# Flyback.net
KiCad netlist of a schematic drawn in Altium Designer
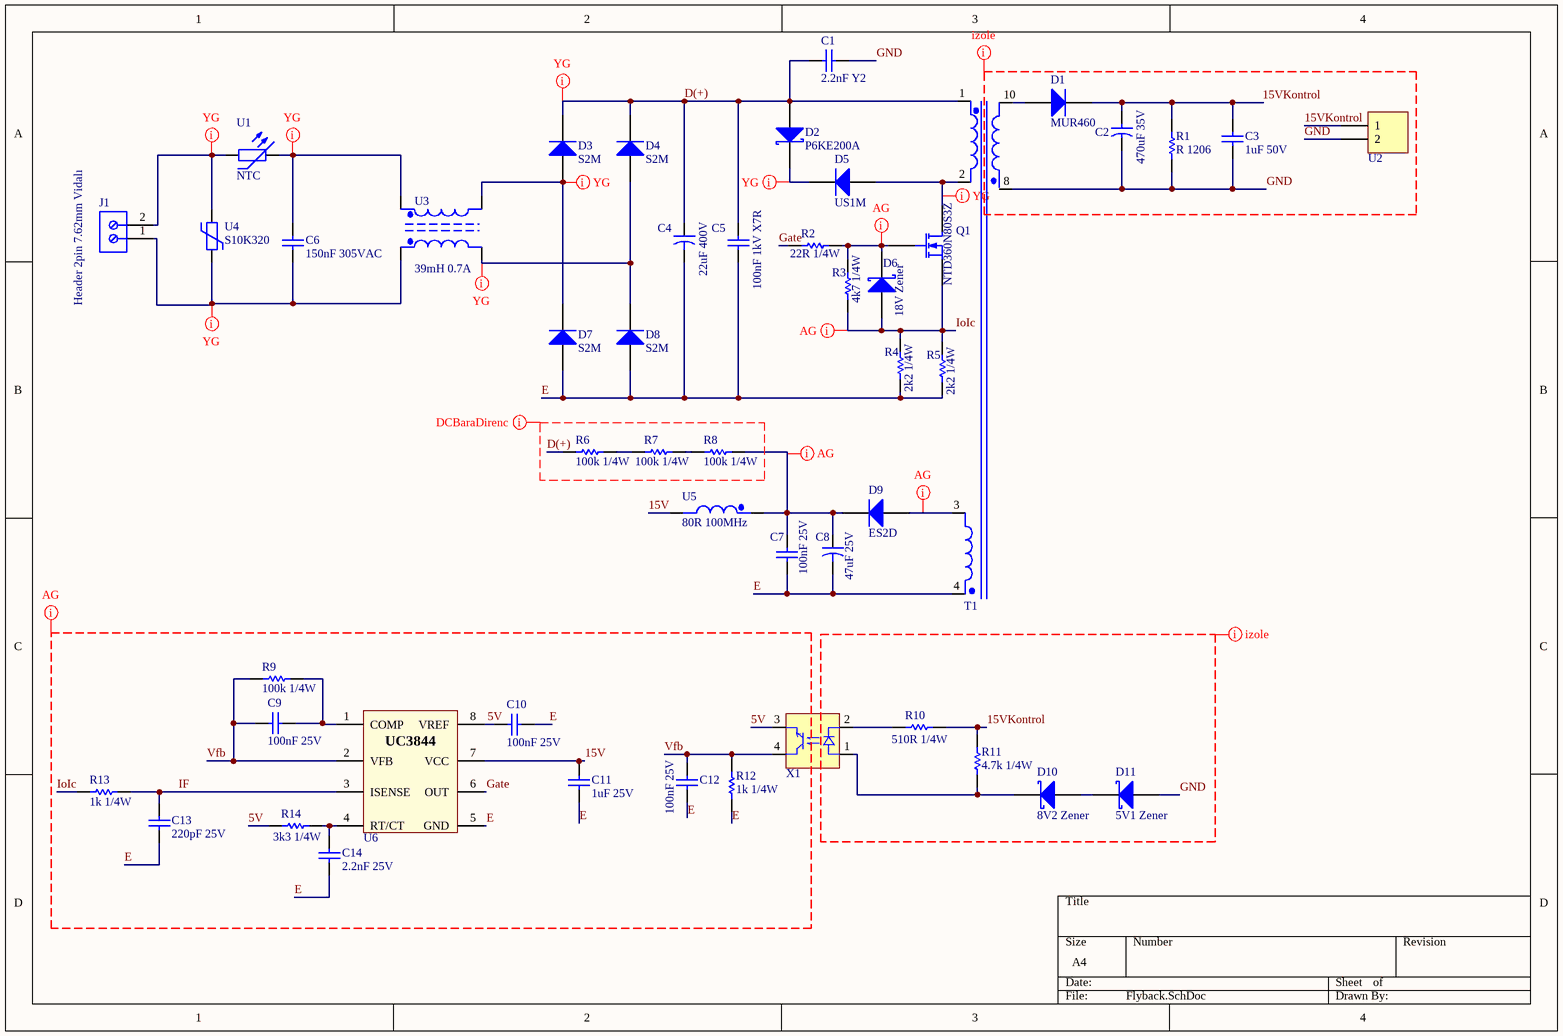
[diagram p0: Flyback.SchDoc]

(export (version "E")
  (design (tool "Eeschema 10.0.6"))
  (components
    (comp (ref "C1")
      (value "2.2nF Y2")
      (footprint "Footprint-Lib-Zhrzkn:4x13x9")
      (description "495-4967-1-ND")
      (fields (field (name "PUBLISHER") "Altium Limited") (field (name "DESIGNER") "ZehraOzkan"))
      (libsource (lib "Schematic-Lib-Zhrzkn") (part "Cap Y2 2.2nF 300V MKP TDK"))
    )
    (comp (ref "C2")
      (value "470uF 35V")
      (footprint "Footprint-Lib-Zhrzkn:CAPPRD500W60D1025H1750")
      (description "860040475008")
      (fields (field (name "PUBLISHER") "Altium Limited") (field (name "DESIGNER") "ZehraOzkan"))
      (libsource (lib "Schematic-Lib-Zhrzkn") (part "C 470uF 35V 1.76A 28mOhm"))
    )
    (comp (ref "C3")
      (value "1uF 50V")
      (footprint "Footprint-Lib-Zhrzkn:1206")
      (description "SMD 1206")
      (fields (field (name "DESIGNER") "ZehraOzkan"))
      (libsource (lib "Schematic-Lib-Zhrzkn") (part "C 1206"))
    )
    (comp (ref "C4")
      (value "22uF 400V")
      (footprint "Footprint-Lib-Zhrzkn:22uF 400V")
      (description "400AX22MEFC12.5X16")
      (fields
        (field (name "MANUFACTURER_PART_NUMBER") "TPSE107K020R0150")
        (field (name "MOUSER PART NUMBER") "581-TPSE107K020R0150")
        (field (name "DESIGNER") "ZehraOzkan")
      )
      (libsource (lib "Schematic-Lib-Zhrzkn") (part "C 22uF 400V 270mArms"))
    )
    (comp (ref "C5")
      (value "100nF 1kV X7R")
      (footprint "RCE7U2J333J5B1H03B")
      (description "490-8944-ND")
      (fields (field (name "PUBLISHER") "Altium Limited") (field (name "DESIGNER") "ZehraOzkan"))
      (libsource (lib "Schematic-Lib-Zhrzkn") (part "C Seramik 100nF 1kV X7R 5mm"))
    )
    (comp (ref "C6")
      (value "150nF 305VAC")
      (footprint "Footprint-Lib-Zhrzkn:CFR F15 L18 B6 H12")
      (description "1572-1789-ND")
      (fields
        (field (name "PART NUMBER") "890273322005CS")
        (field (name "PUBLISHER") "Wurth Elektronik")
        (field (name "DESIGNER") "ZehraOzkan")
      )
      (libsource (lib "Schematic-Lib-Zhrzkn") (part "Cap 150nF 305VAC X2"))
    )
    (comp (ref "C7")
      (value "100nF 25V")
      (footprint "Footprint-Lib-Zhrzkn:1206")
      (description "SMD 1206")
      (fields (field (name "DESIGNER") "ZehraOzkan"))
      (libsource (lib "Schematic-Lib-Zhrzkn") (part "C 1206"))
    )
    (comp (ref "C8")
      (value "47uF 25V")
      (footprint "Footprint-Lib-Zhrzkn:CAPPRD200W50D525H1250")
      (description "1189-1590-1-ND")
      (fields (field (name "DESIGNER") "ZehraOzkan"))
      (libsource (lib "Schematic-Lib-Zhrzkn") (part "C 47uF 25V 250mArms 400mOhm"))
    )
    (comp (ref "C9")
      (value "100nF 25V")
      (footprint "Footprint-Lib-Zhrzkn:1206")
      (description "SMD 1206")
      (fields (field (name "DESIGNER") "ZehraOzkan"))
      (libsource (lib "Schematic-Lib-Zhrzkn") (part "C 1206"))
    )
    (comp (ref "C10")
      (value "100nF 25V")
      (footprint "Footprint-Lib-Zhrzkn:1206")
      (description "SMD 1206")
      (fields (field (name "DESIGNER") "ZehraOzkan"))
      (libsource (lib "Schematic-Lib-Zhrzkn") (part "C 1206"))
    )
    (comp (ref "C11")
      (value "1uF 25V")
      (footprint "Footprint-Lib-Zhrzkn:1206")
      (description "SMD 1206")
      (fields (field (name "DESIGNER") "ZehraOzkan"))
      (libsource (lib "Schematic-Lib-Zhrzkn") (part "C 1206"))
    )
    (comp (ref "C12")
      (value "100nF 25V")
      (footprint "Footprint-Lib-Zhrzkn:1206")
      (description "SMD 1206")
      (fields (field (name "DESIGNER") "ZehraOzkan"))
      (libsource (lib "Schematic-Lib-Zhrzkn") (part "C 1206"))
    )
    (comp (ref "C13")
      (value "220pF 25V")
      (footprint "Footprint-Lib-Zhrzkn:1206")
      (description "SMD 1206")
      (fields (field (name "DESIGNER") "ZehraOzkan"))
      (libsource (lib "Schematic-Lib-Zhrzkn") (part "C 1206"))
    )
    (comp (ref "C14")
      (value "2.2nF 25V")
      (footprint "Footprint-Lib-Zhrzkn:1206")
      (description "SMD 1206")
      (fields (field (name "DESIGNER") "ZehraOzkan"))
      (libsource (lib "Schematic-Lib-Zhrzkn") (part "C 1206"))
    )
    (comp (ref "D1")
      (value "MUR460")
      (footprint "DO-201AD -Dik")
      (description "MUR460RLGOSCT-ND")
      (fields (field (name "DESIGNER") "ZehraOzkan"))
      (libsource (lib "Schematic-Lib-Zhrzkn") (part "Diyot DO-201AD Dik"))
    )
    (comp (ref "D2")
      (value "P6KE200A")
      (footprint "DO-15((DO-204AC)")
      (description "497-13419-1-ND")
      (fields (field (name "PUBLISHER") "Altium Limited") (field (name "DESIGNER") "ZehraOzkan"))
      (libsource (lib "Schematic-Lib-Zhrzkn") (part "TVS 200V DO-15"))
    )
    (comp (ref "D3")
      (value "S2M")
      (footprint "DO-214AA(SMB)")
      (description "1655-1N4007FLCT-ND")
      (fields (field (name "DESIGNER") "ZehraOzkan"))
      (libsource (lib "Schematic-Lib-Zhrzkn") (part "D 1N4007 DO-214AA(SMB)"))
    )
    (comp (ref "D4")
      (value "S2M")
      (footprint "DO-214AA(SMB)")
      (description "1655-1N4007FLCT-ND")
      (fields (field (name "DESIGNER") "ZehraOzkan"))
      (libsource (lib "Schematic-Lib-Zhrzkn") (part "D 1N4007 DO-214AA(SMB)"))
    )
    (comp (ref "D5")
      (value "US1M")
      (footprint "DO-214AA(SMB)")
      (description "SMA")
      (fields (field (name "DESIGNER") "ZehraOzkan"))
      (libsource (lib "Schematic-Lib-Zhrzkn") (part "US1M"))
    )
    (comp (ref "D6")
      (value "18V Zener")
      (footprint "SOD-123")
      (description "SOD-123")
      (fields (field (name "PUBLISHER") "Altium Limited") (field (name "DESIGNER") "ZehraOzkan"))
      (libsource (lib "Schematic-Lib-Zhrzkn") (part "Zener SOD-123_1"))
    )
    (comp (ref "D7")
      (value "S2M")
      (footprint "DO-214AA(SMB)")
      (description "1655-1N4007FLCT-ND")
      (fields (field (name "DESIGNER") "ZehraOzkan"))
      (libsource (lib "Schematic-Lib-Zhrzkn") (part "D 1N4007 DO-214AA(SMB)"))
    )
    (comp (ref "D8")
      (value "S2M")
      (footprint "DO-214AA(SMB)")
      (description "1655-1N4007FLCT-ND")
      (fields (field (name "DESIGNER") "ZehraOzkan"))
      (libsource (lib "Schematic-Lib-Zhrzkn") (part "D 1N4007 DO-214AA(SMB)"))
    )
    (comp (ref "D9")
      (value "ES2D")
      (footprint "DO-214AA(SMB)")
      (description "ES2DFSCT-ND")
      (fields (field (name "DESIGNER") "ZehraOzkan"))
      (libsource (lib "Schematic-Lib-Zhrzkn") (part "D ES2D"))
    )
    (comp (ref "D10")
      (value "8V2 Zener")
      (footprint "SOD-123")
      (description "SOD-123")
      (fields (field (name "PUBLISHER") "Altium Limited") (field (name "DESIGNER") "ZehraOzkan"))
      (libsource (lib "Schematic-Lib-Zhrzkn") (part "Zener SOD-123_1"))
    )
    (comp (ref "D11")
      (value "5V1 Zener")
      (footprint "SOD-123")
      (description "SOD-123")
      (fields (field (name "PUBLISHER") "Altium Limited") (field (name "DESIGNER") "ZehraOzkan"))
      (libsource (lib "Schematic-Lib-Zhrzkn") (part "Zener SOD-123_1"))
    )
    (comp (ref "J1")
      (value "Header 2pin 7.62mm Vidalı")
      (footprint "Header 2 Pin 7.62mm Vidalı")
      (description "691214410002")
      (fields
        (field (name "PART NUMBER") "691218410002")
        (field (name "PUBLISHER") "Wurth Elektronik")
        (field (name "DESIGNER") "ZehraOzkan")
      )
      (libsource (lib "Schematic-Lib-Zhrzkn") (part "Header 2pin 7.62mm Vidalı"))
    )
    (comp (ref "Q1")
      (value "NTD360N80S3Z")
      (footprint "DPAK IGBT")
      (description "DPAK")
      (fields (field (name "PUBLISHER") "Altium Limited") (field (name "DESIGNER") "ZehraOzkan"))
      (libsource (lib "Schematic-Lib-Zhrzkn") (part "MOSFET DPAK"))
    )
    (comp (ref "R1")
      (value "R 1206")
      (footprint "RES_1206")
      (description "SMD 1206")
      (fields (field (name "DESIGNER") "ZehraOzkan"))
      (libsource (lib "Schematic-Lib-Zhrzkn") (part "R 1206"))
    )
    (comp (ref "R2")
      (value "22R 1/4W")
      (footprint "RES_1206")
      (description "SMD 1206")
      (fields (field (name "DESIGNER") "ZehraOzkan"))
      (libsource (lib "Schematic-Lib-Zhrzkn") (part "R 1206"))
    )
    (comp (ref "R3")
      (value "4k7 1/4W")
      (footprint "RES_1206")
      (description "SMD 1206")
      (fields (field (name "DESIGNER") "ZehraOzkan"))
      (libsource (lib "Schematic-Lib-Zhrzkn") (part "R 1206"))
    )
    (comp (ref "R4")
      (value "2k2 1/4W")
      (footprint "RES_1206")
      (description "SMD 1206")
      (fields (field (name "DESIGNER") "ZehraOzkan"))
      (libsource (lib "Schematic-Lib-Zhrzkn") (part "R 1206"))
    )
    (comp (ref "R5")
      (value "2k2 1/4W")
      (footprint "RES_1206")
      (description "SMD 1206")
      (fields (field (name "DESIGNER") "ZehraOzkan"))
      (libsource (lib "Schematic-Lib-Zhrzkn") (part "R 1206"))
    )
    (comp (ref "R6")
      (value "100k 1/4W")
      (footprint "RES_1206")
      (description "SMD 1206")
      (fields (field (name "DESIGNER") "ZehraOzkan"))
      (libsource (lib "Schematic-Lib-Zhrzkn") (part "R 1206"))
    )
    (comp (ref "R7")
      (value "100k 1/4W")
      (footprint "RES_1206")
      (description "SMD 1206")
      (fields (field (name "DESIGNER") "ZehraOzkan"))
      (libsource (lib "Schematic-Lib-Zhrzkn") (part "R 1206"))
    )
    (comp (ref "R8")
      (value "100k 1/4W")
      (footprint "RES_1206")
      (description "SMD 1206")
      (fields (field (name "DESIGNER") "ZehraOzkan"))
      (libsource (lib "Schematic-Lib-Zhrzkn") (part "R 1206"))
    )
    (comp (ref "R9")
      (value "100k 1/4W")
      (footprint "RES_1206")
      (description "SMD 1206")
      (fields (field (name "DESIGNER") "ZehraOzkan"))
      (libsource (lib "Schematic-Lib-Zhrzkn") (part "R 1206"))
    )
    (comp (ref "R10")
      (value "510R 1/4W")
      (footprint "RES_1206")
      (description "SMD 1206")
      (fields (field (name "DESIGNER") "ZehraOzkan"))
      (libsource (lib "Schematic-Lib-Zhrzkn") (part "R 1206"))
    )
    (comp (ref "R11")
      (value "4.7k 1/4W")
      (footprint "RES_1206")
      (description "SMD 1206")
      (fields (field (name "DESIGNER") "ZehraOzkan"))
      (libsource (lib "Schematic-Lib-Zhrzkn") (part "R 1206"))
    )
    (comp (ref "R12")
      (value "1k 1/4W")
      (footprint "RES_1206")
      (description "SMD 1206")
      (fields (field (name "DESIGNER") "ZehraOzkan"))
      (libsource (lib "Schematic-Lib-Zhrzkn") (part "R 1206"))
    )
    (comp (ref "R13")
      (value "1k 1/4W")
      (footprint "RES_1206")
      (description "SMD 1206")
      (fields (field (name "DESIGNER") "ZehraOzkan"))
      (libsource (lib "Schematic-Lib-Zhrzkn") (part "R 1206"))
    )
    (comp (ref "R14")
      (value "3k3 1/4W")
      (footprint "RES_1206")
      (description "SMD 1206")
      (fields (field (name "DESIGNER") "ZehraOzkan"))
      (libsource (lib "Schematic-Lib-Zhrzkn") (part "R 1206"))
    )
    (comp (ref "T1")
      (value "SMPS Tr")
      (footprint "SMPS Tr3")
      (fields (field (name "PUBLISHER") "Altium Limited") (field (name "DESIGNER") "ZehraOzkan"))
      (libsource (lib "Schematic-Lib-Zhrzkn") (part "SMPS Tr EF25"))
    )
    (comp (ref "U1")
      (value "NTC")
      (footprint "NTC B57153S0100")
      (description "495-2076-ND")
      (fields (field (name "PUBLISHER") "Altium Limited") (field (name "DESIGNER") "ZehraOzkan"))
      (libsource (lib "Schematic-Lib-Zhrzkn") (part "NTC 10R 2A 8.5mm"))
    )
    (comp (ref "U2")
      (value "Terminal Blok 2 Pin 2.54mm")
      (footprint "Header 2pin 2.54mm Vidalı")
      (description "691210910002")
      (fields (field (name "PUBLISHER") "Altium Limited") (field (name "DESIGNER") "ZehraOzkan"))
      (libsource (lib "Schematic-Lib-Zhrzkn") (part "Header 2 Pin 2.54mm Vidalı"))
    )
    (comp (ref "U3")
      (value "39mH 0.7A")
      (footprint "EMC SMPS TDK")
      (description "495-2781-ND")
      (fields (field (name "DESIGNER") "ZehraOzkan"))
      (libsource (lib "Schematic-Lib-Zhrzkn") (part "EMC SMPS TDK 39mH 0.7A"))
    )
    (comp (ref "U4")
      (value "S10K320")
      (footprint "Varistor630V")
      (fields (field (name "PUBLISHER") "Altium Limited") (field (name "DESIGNER") "ZehraOzkan"))
      (libsource (lib "Schematic-Lib-Zhrzkn") (part "Varistor S10K320"))
    )
    (comp (ref "U5")
      (value "80R 100MHz")
      (footprint "Footprint-Lib-Zhrzkn:1206 Bead")
      (description "SMD 1206")
      (fields (field (name "DESIGNER") "ZehraOzkan"))
      (libsource (lib "Schematic-Lib-Zhrzkn") (part "Bead 1206"))
    )
    (comp (ref "U6")
      (value "UC3844")
      (footprint "SOIC-OA8_L")
      (description "SOIC8")
      (fields (field (name "DESIGNER") "ZehraOzkan"))
      (libsource (lib "Schematic-Lib-Zhrzkn") (part "UC3844"))
    )
    (comp (ref "X1")
      (value "PC81710NIP1B")
      (footprint "PC817 SMD")
      (description "1855-1014-1-ND")
      (fields (field (name "DESIGNER") "ZehraOzkan"))
      (libsource (lib "Schematic-Lib-Zhrzkn") (part "PC817"))
    )
  )
  (nets
    (net (code "1") (name "/5V") (class "Default")
      (node (ref "C10") (pin "1") (pinfunction "1_1") (pintype "passive"))
      (node (ref "R14") (pin "1") (pinfunction "1_1") (pintype "passive"))
      (node (ref "U6") (pin "8") (pinfunction "VREF_8") (pintype "passive"))
      (node (ref "X1") (pin "3") (pinfunction "E_3") (pintype "passive"))
    )
    (net (code "2") (name "/15V") (class "Default")
      (node (ref "C11") (pin "2") (pinfunction "2_2") (pintype "passive"))
      (node (ref "U5") (pin "2") (pinfunction "2_2") (pintype "passive"))
      (node (ref "U6") (pin "7") (pinfunction "VCC_7") (pintype "passive"))
    )
    (net (code "3") (name "/15VKontrol") (class "Default")
      (node (ref "C2") (pin "1") (pinfunction "1_1") (pintype "passive"))
      (node (ref "C3") (pin "2") (pinfunction "2_2") (pintype "passive"))
      (node (ref "D1") (pin "2") (pinfunction "K_2") (pintype "passive"))
      (node (ref "R1") (pin "2") (pinfunction "2_2") (pintype "passive"))
      (node (ref "R10") (pin "1") (pinfunction "1_1") (pintype "passive"))
      (node (ref "R11") (pin "1") (pinfunction "1_1") (pintype "passive"))
      (node (ref "U2") (pin "1") (pinfunction "1_1") (pintype "passive"))
    )
    (net (code "4") (name "/D(+)") (class "Default")
      (node (ref "C1") (pin "1") (pinfunction "1_1") (pintype "passive"))
      (node (ref "C4") (pin "1") (pinfunction "1_1") (pintype "passive"))
      (node (ref "C5") (pin "2") (pinfunction "2_2") (pintype "passive"))
      (node (ref "D2") (pin "1") (pinfunction "A_1") (pintype "passive"))
      (node (ref "D3") (pin "2") (pinfunction "K_2") (pintype "passive"))
      (node (ref "D4") (pin "2") (pinfunction "K_2") (pintype "passive"))
      (node (ref "R6") (pin "1") (pinfunction "1_1") (pintype "passive"))
      (node (ref "T1") (pin "1") (pinfunction "Pri+_1") (pintype "passive"))
    )
    (net (code "5") (name "/E") (class "Default")
      (node (ref "C10") (pin "2") (pinfunction "2_2") (pintype "passive"))
      (node (ref "C11") (pin "1") (pinfunction "1_1") (pintype "passive"))
      (node (ref "C12") (pin "1") (pinfunction "1_1") (pintype "passive"))
      (node (ref "C13") (pin "2") (pinfunction "2_2") (pintype "passive"))
      (node (ref "C14") (pin "2") (pinfunction "2_2") (pintype "passive"))
      (node (ref "C4") (pin "2") (pinfunction "2_2") (pintype "passive"))
      (node (ref "C5") (pin "1") (pinfunction "1_1") (pintype "passive"))
      (node (ref "C7") (pin "1") (pinfunction "1_1") (pintype "passive"))
      (node (ref "C8") (pin "2") (pinfunction "2_2") (pintype "passive"))
      (node (ref "D7") (pin "1") (pinfunction "A_1") (pintype "passive"))
      (node (ref "D8") (pin "1") (pinfunction "A_1") (pintype "passive"))
      (node (ref "R12") (pin "1") (pinfunction "1_1") (pintype "passive"))
      (node (ref "R4") (pin "1") (pinfunction "1_1") (pintype "passive"))
      (node (ref "R5") (pin "1") (pinfunction "1_1") (pintype "passive"))
      (node (ref "T1") (pin "4") (pinfunction "Sec3-_4") (pintype "passive"))
      (node (ref "U6") (pin "5") (pinfunction "GND_5") (pintype "power_in"))
    )
    (net (code "6") (name "/GND") (class "Default")
      (node (ref "C1") (pin "2") (pinfunction "2_2") (pintype "passive"))
      (node (ref "C2") (pin "2") (pinfunction "2_2") (pintype "passive"))
      (node (ref "C3") (pin "1") (pinfunction "1_1") (pintype "passive"))
      (node (ref "D11") (pin "1") (pinfunction "A_1") (pintype "passive"))
      (node (ref "R1") (pin "1") (pinfunction "1_1") (pintype "passive"))
      (node (ref "T1") (pin "8") (pinfunction "8_8") (pintype "passive"))
      (node (ref "U2") (pin "2") (pinfunction "2_2") (pintype "passive"))
    )
    (net (code "7") (name "/Gate") (class "Default")
      (node (ref "R2") (pin "2") (pinfunction "2_2") (pintype "passive"))
      (node (ref "U6") (pin "6") (pinfunction "OUT_6") (pintype "power_in"))
    )
    (net (code "8") (name "/IF") (class "Default")
      (node (ref "C13") (pin "1") (pinfunction "1_1") (pintype "passive"))
      (node (ref "R13") (pin "2") (pinfunction "2_2") (pintype "passive"))
      (node (ref "U6") (pin "3") (pinfunction "ISENSE_3") (pintype "passive"))
    )
    (net (code "9") (name "/IoIc") (class "Default")
      (node (ref "D6") (pin "1") (pinfunction "A_1") (pintype "passive"))
      (node (ref "Q1") (pin "3") (pinfunction "S_3") (pintype "passive"))
      (node (ref "R13") (pin "1") (pinfunction "1_1") (pintype "passive"))
      (node (ref "R3") (pin "1") (pinfunction "1_1") (pintype "passive"))
      (node (ref "R4") (pin "2") (pinfunction "2_2") (pintype "passive"))
      (node (ref "R5") (pin "2") (pinfunction "2_2") (pintype "passive"))
    )
    (net (code "10") (name "/Vfb") (class "Default")
      (node (ref "C12") (pin "2") (pinfunction "2_2") (pintype "passive"))
      (node (ref "C9") (pin "2") (pinfunction "2_2") (pintype "passive"))
      (node (ref "R12") (pin "2") (pinfunction "2_2") (pintype "passive"))
      (node (ref "R9") (pin "1") (pinfunction "1_1") (pintype "passive"))
      (node (ref "U6") (pin "2") (pinfunction "VFB_2") (pintype "passive"))
      (node (ref "X1") (pin "4") (pinfunction "C_4") (pintype "passive"))
    )
    (net (code "11") (name "Net-(C6-Pad1)") (class "Default")
      (node (ref "C6") (pin "1") (pinfunction "1_1") (pintype "passive"))
      (node (ref "J1") (pin "1") (pinfunction "1_1") (pintype "passive"))
      (node (ref "U3") (pin "1") (pinfunction "1_1") (pintype "passive"))
      (node (ref "U4") (pin "1") (pinfunction "1_1") (pintype "passive"))
    )
    (net (code "12") (name "Net-(C6-Pad2)") (class "Default")
      (node (ref "C6") (pin "2") (pinfunction "2_2") (pintype "passive"))
      (node (ref "U1") (pin "2") (pinfunction "2_2") (pintype "passive"))
      (node (ref "U3") (pin "2") (pinfunction "2_2") (pintype "passive"))
    )
    (net (code "13") (name "Net-(D1-A)") (class "Default")
      (node (ref "D1") (pin "1") (pinfunction "A_1") (pintype "passive"))
      (node (ref "T1") (pin "10") (pinfunction "Sec1+_10") (pintype "passive"))
    )
    (net (code "14") (name "Net-(D2-K)") (class "Default")
      (node (ref "D2") (pin "2") (pinfunction "K_2") (pintype "passive"))
      (node (ref "D5") (pin "2") (pinfunction "K_2") (pintype "passive"))
    )
    (net (code "15") (name "Net-(D3-A)") (class "Default")
      (node (ref "D3") (pin "1") (pinfunction "A_1") (pintype "passive"))
      (node (ref "D7") (pin "2") (pinfunction "K_2") (pintype "passive"))
      (node (ref "U3") (pin "3") (pinfunction "3_3") (pintype "passive"))
    )
    (net (code "16") (name "Net-(D4-A)") (class "Default")
      (node (ref "D4") (pin "1") (pinfunction "A_1") (pintype "passive"))
      (node (ref "D8") (pin "2") (pinfunction "K_2") (pintype "passive"))
      (node (ref "U3") (pin "4") (pinfunction "4_4") (pintype "passive"))
    )
    (net (code "17") (name "Net-(D5-A)") (class "Default")
      (node (ref "D5") (pin "1") (pinfunction "A_1") (pintype "passive"))
      (node (ref "Q1") (pin "2") (pinfunction "D_2") (pintype "passive"))
      (node (ref "T1") (pin "2") (pinfunction "Pri-_2") (pintype "passive"))
    )
    (net (code "18") (name "Net-(D6-K)") (class "Default")
      (node (ref "D6") (pin "2") (pinfunction "K_2") (pintype "passive"))
      (node (ref "Q1") (pin "1") (pinfunction "G_1") (pintype "passive"))
      (node (ref "R2") (pin "1") (pinfunction "1_1") (pintype "passive"))
      (node (ref "R3") (pin "2") (pinfunction "2_2") (pintype "passive"))
    )
    (net (code "19") (name "Net-(D9-A)") (class "Default")
      (node (ref "D9") (pin "1") (pinfunction "A_1") (pintype "passive"))
      (node (ref "T1") (pin "3") (pinfunction "Sec3+_3") (pintype "passive"))
    )
    (net (code "20") (name "Net-(D9-K)") (class "Default")
      (node (ref "C7") (pin "2") (pinfunction "2_2") (pintype "passive"))
      (node (ref "C8") (pin "1") (pinfunction "1_1") (pintype "passive"))
      (node (ref "D9") (pin "2") (pinfunction "K_2") (pintype "passive"))
      (node (ref "R8") (pin "2") (pinfunction "2_2") (pintype "passive"))
      (node (ref "U5") (pin "1") (pinfunction "1_1") (pintype "passive"))
    )
    (net (code "21") (name "Net-(D10-A)") (class "Default")
      (node (ref "D10") (pin "1") (pinfunction "A_1") (pintype "passive"))
      (node (ref "D11") (pin "2") (pinfunction "K_2") (pintype "passive"))
    )
    (net (code "22") (name "Net-(D10-K)") (class "Default")
      (node (ref "D10") (pin "2") (pinfunction "K_2") (pintype "passive"))
      (node (ref "R11") (pin "2") (pinfunction "2_2") (pintype "passive"))
      (node (ref "X1") (pin "1") (pinfunction "A_1") (pintype "passive"))
    )
    (net (code "23") (name "Net-(J1-Pad2)") (class "Default")
      (node (ref "J1") (pin "2") (pinfunction "2_2") (pintype "passive"))
      (node (ref "U1") (pin "1") (pinfunction "1_1") (pintype "passive"))
      (node (ref "U4") (pin "2") (pinfunction "2_2") (pintype "passive"))
    )
    (net (code "24") (name "Net-(R6-Pad2)") (class "Default")
      (node (ref "R6") (pin "2") (pinfunction "2_2") (pintype "passive"))
      (node (ref "R7") (pin "1") (pinfunction "1_1") (pintype "passive"))
    )
    (net (code "25") (name "Net-(R7-Pad2)") (class "Default")
      (node (ref "R7") (pin "2") (pinfunction "2_2") (pintype "passive"))
      (node (ref "R8") (pin "1") (pinfunction "1_1") (pintype "passive"))
    )
    (net (code "26") (name "Net-(U6-COMP)") (class "Default")
      (node (ref "C9") (pin "1") (pinfunction "1_1") (pintype "passive"))
      (node (ref "R9") (pin "2") (pinfunction "2_2") (pintype "passive"))
      (node (ref "U6") (pin "1") (pinfunction "COMP_1") (pintype "power_in"))
    )
    (net (code "27") (name "Net-(U6-RT{slash}CT)") (class "Default")
      (node (ref "C14") (pin "1") (pinfunction "1_1") (pintype "passive"))
      (node (ref "R14") (pin "2") (pinfunction "2_2") (pintype "passive"))
      (node (ref "U6") (pin "4") (pinfunction "RT/CT_4") (pintype "power_in"))
    )
    (net (code "28") (name "Net-(X1-K)") (class "Default")
      (node (ref "R10") (pin "2") (pinfunction "2_2") (pintype "passive"))
      (node (ref "X1") (pin "2") (pinfunction "K_2") (pintype "passive"))
    )
  )
)
